# 6502.net
KiCad netlist of a schematic drawn in EasyEDA
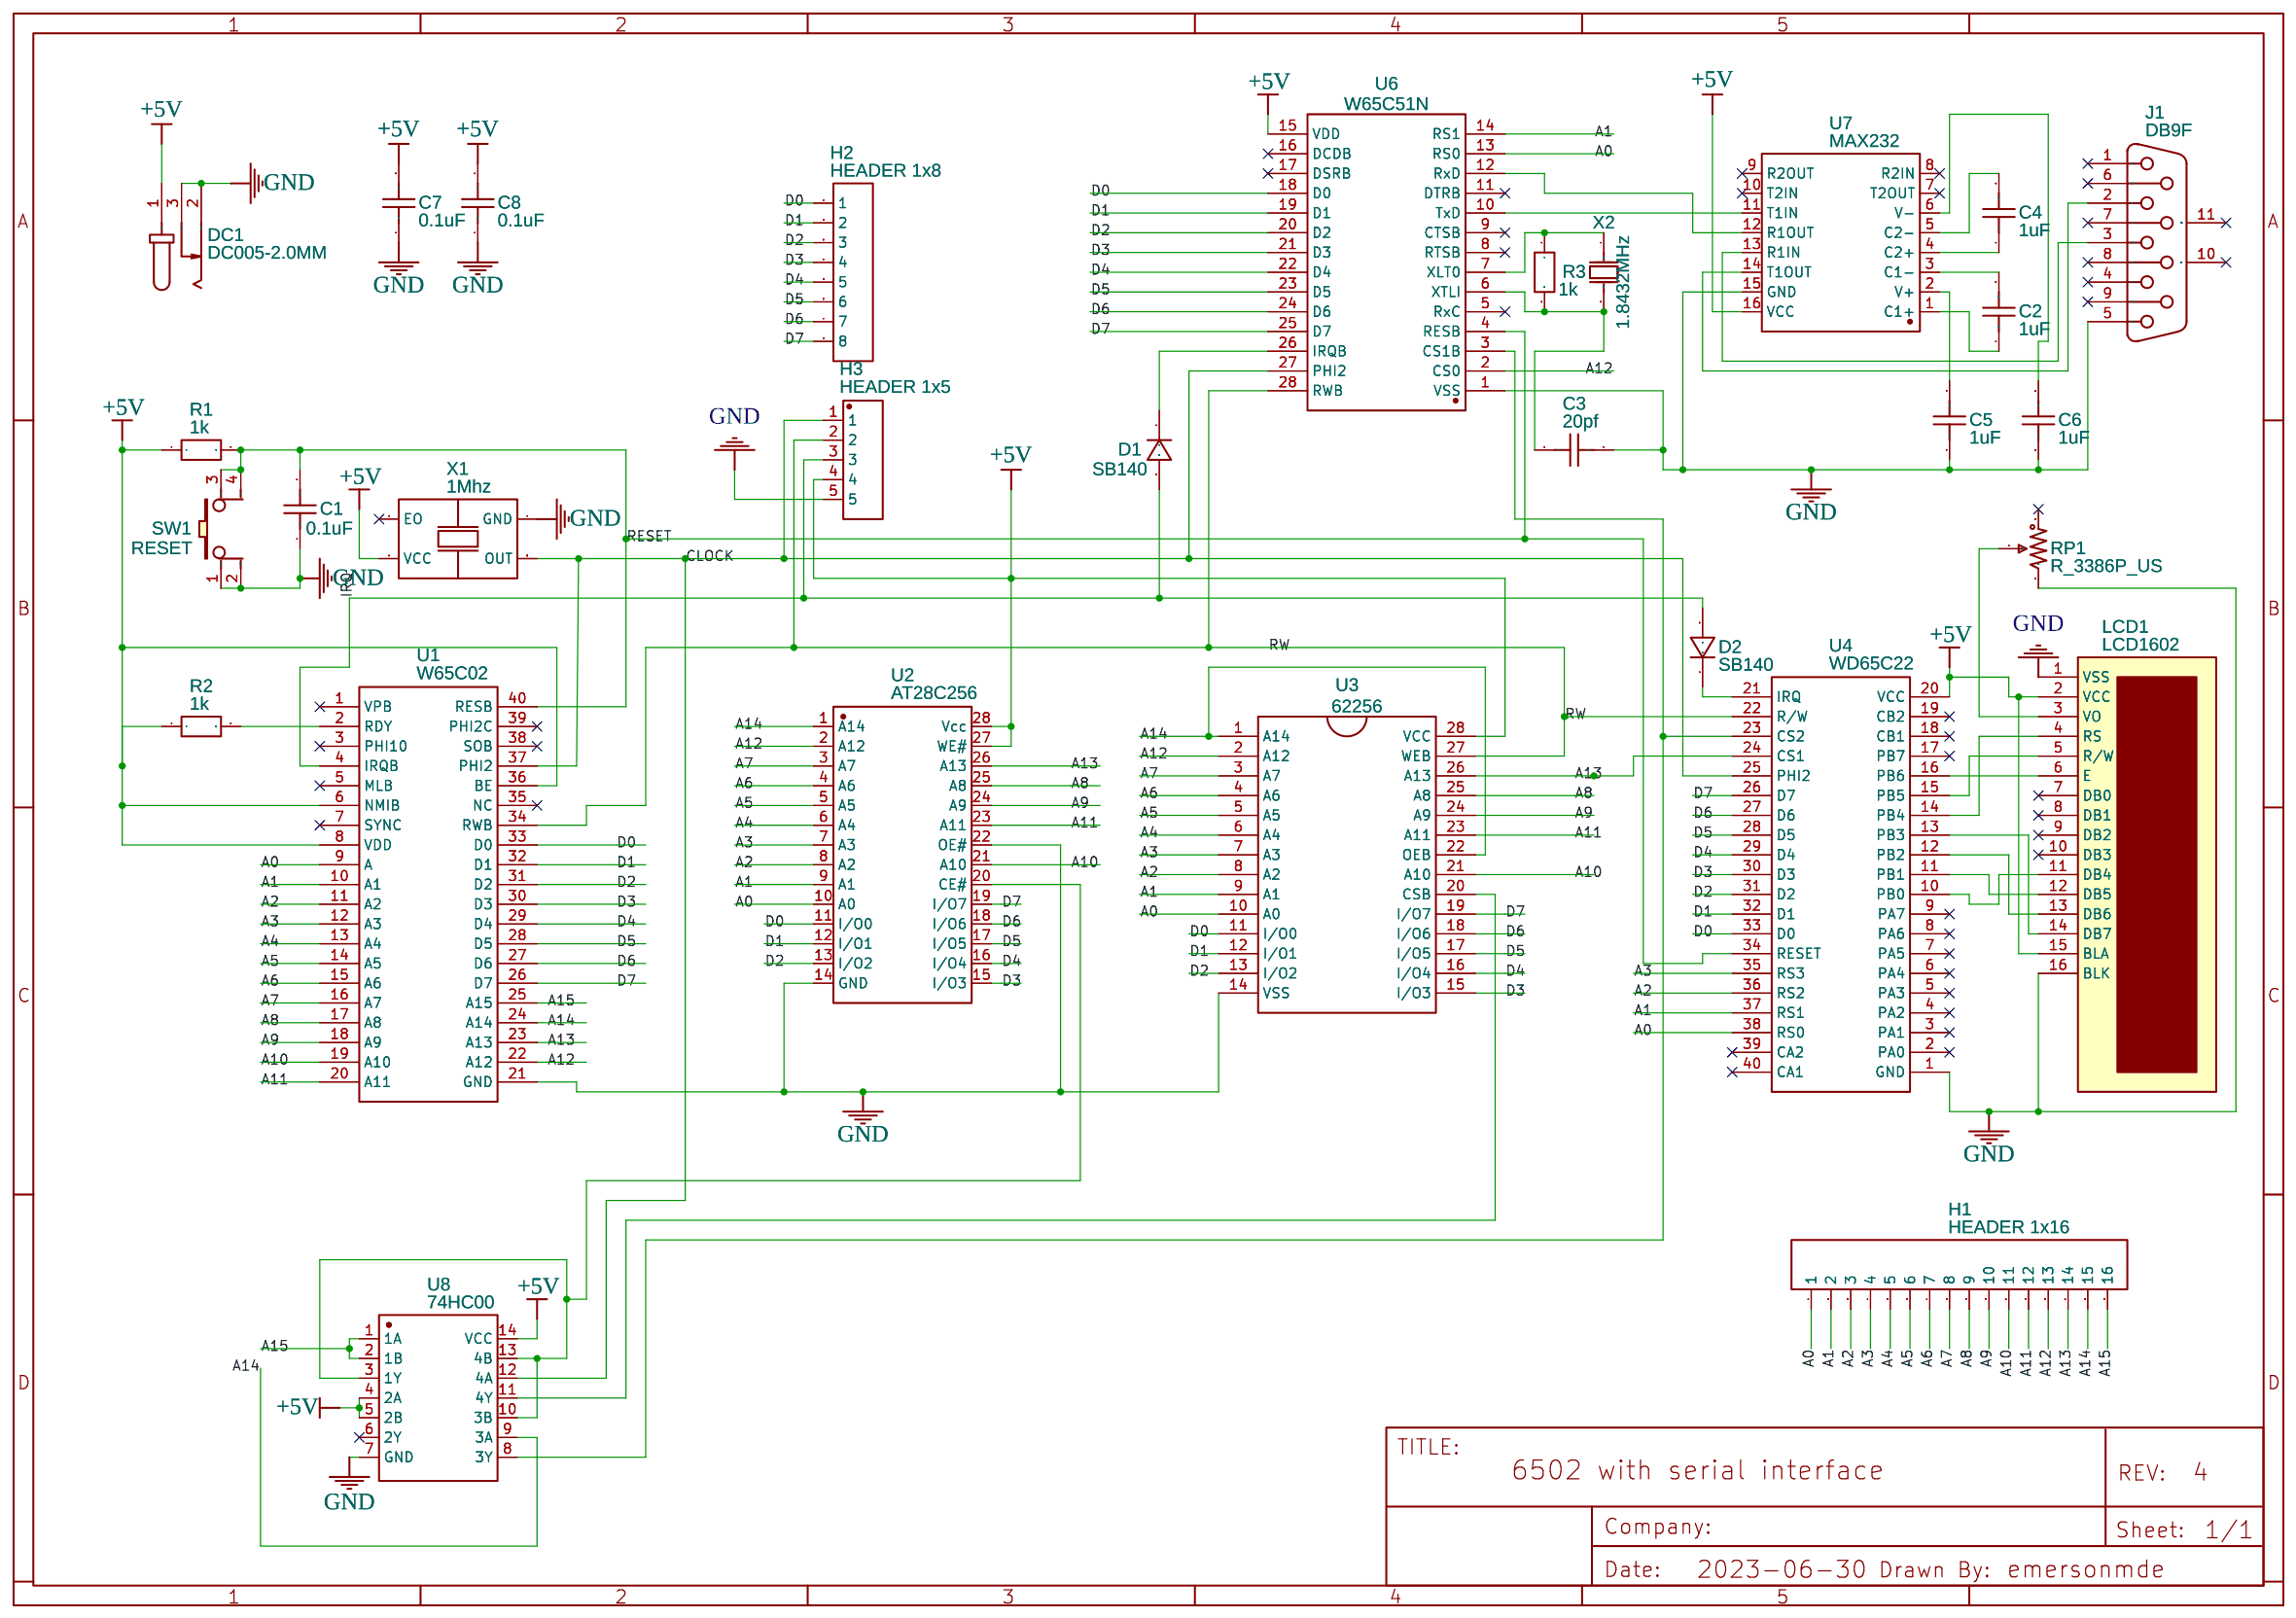
[diagram p0: schematic sheet]

(export (version "E")
  (design (tool "Eeschema 10.0.6"))
  (components
    (comp (ref "C1") (value "0.1uF") (libsource (lib "") (part "C_0603_US")))
    (comp (ref "C2") (value "1uF") (libsource (lib "") (part "C_0603_US")))
    (comp (ref "C3") (value "20pf") (libsource (lib "") (part "C_0603_US_1")))
    (comp (ref "C4") (value "1uF") (libsource (lib "") (part "C_0603_US")))
    (comp (ref "C5") (value "1uF") (libsource (lib "") (part "C_0603_US")))
    (comp (ref "C6") (value "1uF") (libsource (lib "") (part "C_0603_US")))
    (comp (ref "C7") (value "0.1uF") (libsource (lib "") (part "C_0603_US")))
    (comp (ref "C8") (value "0.1uF") (libsource (lib "") (part "C_0603_US")))
    (comp (ref "D1")
      (value "SB140")
      (fields (field (name "BOM_Manufacturer Part") "1N4007W") (field (name "BOM_Supplier Part") "C328592"))
      (libsource (lib "") (part "1N4007W"))
    )
    (comp (ref "D2")
      (value "SB140")
      (fields (field (name "BOM_Manufacturer Part") "1N4007W") (field (name "BOM_Supplier Part") "C328592"))
      (libsource (lib "") (part "1N4007W_1"))
    )
    (comp (ref "DC1")
      (value "DC005-2.0MM")
      (fields (field (name "BOM_Supplier Part") "C111567"))
      (libsource (lib "") (part "DC005-2.0MM"))
    )
    (comp (ref "H1")
      (value "HEADER 1x16")
      (fields
        (field (name "BOM_Manufacturer Part") "2.54-1*16P母")
        (field (name "BOM_Supplier Part") "C66987")
      )
      (libsource (lib "") (part "Header-Female-2.54_1x16"))
    )
    (comp (ref "H2")
      (value "HEADER 1x8")
      (fields
        (field (name "BOM_Manufacturer Part") "2.54-1*8P母环保")
        (field (name "BOM_Supplier Part") "C27438")
      )
      (libsource (lib "") (part "Header-Female-2.54_1x8"))
    )
    (comp (ref "H3") (value "HEADER 1x5") (libsource (lib "") (part "HEADER - 2.54_1X5")))
    (comp (ref "J1")
      (value "DB9F")
      (fields (field (name "BOM_Supplier Part") "C9900018961"))
      (libsource (lib "") (part "DB9F"))
    )
    (comp (ref "LCD1")
      (value "LCD1602")
      (fields
        (field (name "BOM_Manufacturer Part") "LCM1602K-NSW-BBW")
        (field (name "BOM_Supplier Part") "C83275")
      )
      (libsource (lib "") (part "LCD1602"))
    )
    (comp (ref "R1") (value "1k") (libsource (lib "") (part "R_0603_EU")))
    (comp (ref "R2") (value "1k") (libsource (lib "") (part "R_0603_EU")))
    (comp (ref "R3") (value "1k") (libsource (lib "") (part "R_0603_EU_1")))
    (comp (ref "RP1") (value "R_3386P_US") (libsource (lib "") (part "R_3386P_US")))
    (comp (ref "SW1")
      (value "RESET")
      (fields
        (field (name "BOM_Manufacturer Part") "button6*6*8.5")
        (field (name "BOM_Supplier Part") "C59980")
      )
      (libsource (lib "") (part "button6*6*8.5"))
    )
    (comp (ref "U1") (value "W65C02") (libsource (lib "") (part "W65C02")))
    (comp (ref "U2")
      (value "AT28C256")
      (fields
        (field (name "BOM_Manufacturer Part") "AT28C256-15DM/883-815")
        (field (name "BOM_Supplier Part") "C612358")
      )
      (libsource (lib "") (part "AT28C256-15DM/883-815"))
    )
    (comp (ref "U3") (value "62256") (libsource (lib "") (part "HM62256B")))
    (comp (ref "U4") (value "WD65C22") (libsource (lib "") (part "WD65C22")))
    (comp (ref "U6")
      (value "W65C51N")
      (fields
        (field (name "BOM_Manufacturer Part") "W65C51N6TPG-14")
        (field (name "BOM_Supplier Part") "955-W65C51N6TPG-14")
      )
      (libsource (lib "") (part "W65C51N6TPG-14"))
    )
    (comp (ref "U7")
      (value "MAX232")
      (fields
        (field (name "BOM_Manufacturer Part") "MAX232AEPE+")
        (field (name "BOM_Supplier Part") "C242610")
      )
      (libsource (lib "") (part "MAX232AEPE+"))
    )
    (comp (ref "U8")
      (value "74HC00")
      (fields (field (name "BOM_Manufacturer Part") "SN74HC00N") (field (name "BOM_Supplier Part") "C2902"))
      (libsource (lib "") (part "SN74HC00N"))
    )
    (comp (ref "X1")
      (value "1Mhz")
      (fields
        (field (name "BOM_Manufacturer Part") "MXO45-3C-7M372800")
        (field (name "BOM_Supplier Part") "110-MXO45-3C-7M372800-ND")
      )
      (libsource (lib "") (part "Full Can Oscillator Crystal"))
    )
    (comp (ref "X2")
      (value "1.8432MHz")
      (fields
        (field (name "BOM_Manufacturer Part") "X49UD18432MSD2SC-1")
        (field (name "BOM_Supplier Part") "C2179")
      )
      (libsource (lib "") (part "X49UD18432MSD2SC-1 COPY"))
    )
  )
  (nets
    (net (code "1") (name "+5V") (class "Default")
      (node (ref "C7") (pin "2") (pinfunction "2_2") (pintype "unspecified"))
      (node (ref "C8") (pin "2") (pinfunction "2_2") (pintype "unspecified"))
      (node (ref "DC1") (pin "1") (pinfunction "1_1") (pintype "unspecified"))
      (node (ref "H3") (pin "4") (pinfunction "4_4") (pintype "unspecified"))
      (node (ref "LCD1") (pin "15") (pinfunction "BLA_15") (pintype "unspecified"))
      (node (ref "LCD1") (pin "2") (pinfunction "VCC_2") (pintype "unspecified"))
      (node (ref "R1") (pin "1") (pinfunction "1_1") (pintype "unspecified"))
      (node (ref "R2") (pin "1") (pinfunction "1_1") (pintype "unspecified"))
      (node (ref "U1") (pin "36") (pinfunction "BE_36") (pintype "unspecified"))
      (node (ref "U1") (pin "6") (pinfunction "NMIB_6") (pintype "unspecified"))
      (node (ref "U1") (pin "8") (pinfunction "VDD_8") (pintype "unspecified"))
      (node (ref "U2") (pin "27") (pinfunction "WE#_27") (pintype "unspecified"))
      (node (ref "U2") (pin "28") (pinfunction "Vcc_28") (pintype "unspecified"))
      (node (ref "U3") (pin "28") (pinfunction "VCC_28") (pintype "unspecified"))
      (node (ref "U4") (pin "20") (pinfunction "VCC_20") (pintype "unspecified"))
      (node (ref "U6") (pin "15") (pinfunction "VDD_15") (pintype "passive"))
      (node (ref "U7") (pin "16") (pinfunction "VCC_16") (pintype "unspecified"))
      (node (ref "U8") (pin "14") (pinfunction "VCC_14") (pintype "unspecified"))
      (node (ref "U8") (pin "4") (pinfunction "2A_4") (pintype "unspecified"))
      (node (ref "U8") (pin "5") (pinfunction "2B_5") (pintype "unspecified"))
      (node (ref "X1") (pin "14") (pinfunction "VCC_14") (pintype "unspecified"))
    )
    (net (code "2") (name "/A0") (class "Default")
      (node (ref "H1") (pin "1") (pinfunction "1_1") (pintype "input"))
      (node (ref "U1") (pin "9") (pinfunction "A_9") (pintype "unspecified"))
      (node (ref "U2") (pin "10") (pinfunction "A0_10") (pintype "unspecified"))
      (node (ref "U3") (pin "10") (pinfunction "A0_10") (pintype "unspecified"))
      (node (ref "U4") (pin "38") (pinfunction "RS0_38") (pintype "unspecified"))
      (node (ref "U6") (pin "13") (pinfunction "RS0_13") (pintype "unspecified"))
    )
    (net (code "3") (name "/A1") (class "Default")
      (node (ref "H1") (pin "2") (pinfunction "2_2") (pintype "input"))
      (node (ref "U1") (pin "10") (pinfunction "A1_10") (pintype "unspecified"))
      (node (ref "U2") (pin "9") (pinfunction "A1_9") (pintype "unspecified"))
      (node (ref "U3") (pin "9") (pinfunction "A1_9") (pintype "unspecified"))
      (node (ref "U4") (pin "37") (pinfunction "RS1_37") (pintype "unspecified"))
      (node (ref "U6") (pin "14") (pinfunction "RS1_14") (pintype "unspecified"))
    )
    (net (code "4") (name "/A2") (class "Default")
      (node (ref "H1") (pin "3") (pinfunction "3_3") (pintype "input"))
      (node (ref "U1") (pin "11") (pinfunction "A2_11") (pintype "unspecified"))
      (node (ref "U2") (pin "8") (pinfunction "A2_8") (pintype "unspecified"))
      (node (ref "U3") (pin "8") (pinfunction "A2_8") (pintype "unspecified"))
      (node (ref "U4") (pin "36") (pinfunction "RS2_36") (pintype "unspecified"))
    )
    (net (code "5") (name "/A3") (class "Default")
      (node (ref "H1") (pin "4") (pinfunction "4_4") (pintype "input"))
      (node (ref "U1") (pin "12") (pinfunction "A3_12") (pintype "unspecified"))
      (node (ref "U2") (pin "7") (pinfunction "A3_7") (pintype "unspecified"))
      (node (ref "U3") (pin "7") (pinfunction "A3_7") (pintype "unspecified"))
      (node (ref "U4") (pin "35") (pinfunction "RS3_35") (pintype "unspecified"))
    )
    (net (code "6") (name "/A4") (class "Default")
      (node (ref "H1") (pin "5") (pinfunction "5_5") (pintype "input"))
      (node (ref "U1") (pin "13") (pinfunction "A4_13") (pintype "unspecified"))
      (node (ref "U2") (pin "6") (pinfunction "A4_6") (pintype "unspecified"))
      (node (ref "U3") (pin "6") (pinfunction "A4_6") (pintype "unspecified"))
    )
    (net (code "7") (name "/A5") (class "Default")
      (node (ref "H1") (pin "6") (pinfunction "6_6") (pintype "input"))
      (node (ref "U1") (pin "14") (pinfunction "A5_14") (pintype "unspecified"))
      (node (ref "U2") (pin "5") (pinfunction "A5_5") (pintype "unspecified"))
      (node (ref "U3") (pin "5") (pinfunction "A5_5") (pintype "unspecified"))
    )
    (net (code "8") (name "/A6") (class "Default")
      (node (ref "H1") (pin "7") (pinfunction "7_7") (pintype "input"))
      (node (ref "U1") (pin "15") (pinfunction "A6_15") (pintype "unspecified"))
      (node (ref "U2") (pin "4") (pinfunction "A6_4") (pintype "unspecified"))
      (node (ref "U3") (pin "4") (pinfunction "A6_4") (pintype "unspecified"))
    )
    (net (code "9") (name "/A7") (class "Default")
      (node (ref "H1") (pin "8") (pinfunction "8_8") (pintype "input"))
      (node (ref "U1") (pin "16") (pinfunction "A7_16") (pintype "unspecified"))
      (node (ref "U2") (pin "3") (pinfunction "A7_3") (pintype "unspecified"))
      (node (ref "U3") (pin "3") (pinfunction "A7_3") (pintype "unspecified"))
    )
    (net (code "10") (name "/A8") (class "Default")
      (node (ref "H1") (pin "9") (pinfunction "9_9") (pintype "input"))
      (node (ref "U1") (pin "17") (pinfunction "A8_17") (pintype "unspecified"))
      (node (ref "U2") (pin "25") (pinfunction "A8_25") (pintype "unspecified"))
      (node (ref "U3") (pin "25") (pinfunction "A8_25") (pintype "unspecified"))
    )
    (net (code "11") (name "/A9") (class "Default")
      (node (ref "H1") (pin "10") (pinfunction "10_10") (pintype "input"))
      (node (ref "U1") (pin "18") (pinfunction "A9_18") (pintype "unspecified"))
      (node (ref "U2") (pin "24") (pinfunction "A9_24") (pintype "unspecified"))
      (node (ref "U3") (pin "24") (pinfunction "A9_24") (pintype "unspecified"))
    )
    (net (code "12") (name "/A10") (class "Default")
      (node (ref "H1") (pin "11") (pinfunction "11_11") (pintype "input"))
      (node (ref "U1") (pin "19") (pinfunction "A10_19") (pintype "unspecified"))
      (node (ref "U2") (pin "21") (pinfunction "A10_21") (pintype "unspecified"))
      (node (ref "U3") (pin "21") (pinfunction "A10_21") (pintype "unspecified"))
    )
    (net (code "13") (name "/A11") (class "Default")
      (node (ref "H1") (pin "12") (pinfunction "12_12") (pintype "input"))
      (node (ref "U1") (pin "20") (pinfunction "A11_20") (pintype "unspecified"))
      (node (ref "U2") (pin "23") (pinfunction "A11_23") (pintype "unspecified"))
      (node (ref "U3") (pin "23") (pinfunction "A11_23") (pintype "unspecified"))
    )
    (net (code "14") (name "/A12") (class "Default")
      (node (ref "H1") (pin "13") (pinfunction "13_13") (pintype "input"))
      (node (ref "U1") (pin "22") (pinfunction "A12_22") (pintype "unspecified"))
      (node (ref "U2") (pin "2") (pinfunction "A12_2") (pintype "unspecified"))
      (node (ref "U3") (pin "2") (pinfunction "A12_2") (pintype "unspecified"))
      (node (ref "U6") (pin "2") (pinfunction "CS0_2") (pintype "unspecified"))
    )
    (net (code "15") (name "/A13") (class "Default")
      (node (ref "H1") (pin "14") (pinfunction "14_14") (pintype "input"))
      (node (ref "U1") (pin "23") (pinfunction "A13_23") (pintype "unspecified"))
      (node (ref "U2") (pin "26") (pinfunction "A13_26") (pintype "unspecified"))
      (node (ref "U3") (pin "26") (pinfunction "A13_26") (pintype "unspecified"))
      (node (ref "U4") (pin "24") (pinfunction "CS1_24") (pintype "unspecified"))
    )
    (net (code "16") (name "/A14") (class "Default")
      (node (ref "H1") (pin "15") (pinfunction "15_15") (pintype "input"))
      (node (ref "U1") (pin "24") (pinfunction "A14_24") (pintype "unspecified"))
      (node (ref "U2") (pin "1") (pinfunction "A14_1") (pintype "unspecified"))
      (node (ref "U3") (pin "1") (pinfunction "A14_1") (pintype "unspecified"))
      (node (ref "U3") (pin "22") (pinfunction "OEB_22") (pintype "unspecified"))
      (node (ref "U8") (pin "9") (pinfunction "3A_9") (pintype "unspecified"))
    )
    (net (code "17") (name "/A15") (class "Default")
      (node (ref "H1") (pin "16") (pinfunction "16_16") (pintype "input"))
      (node (ref "U1") (pin "25") (pinfunction "A15_25") (pintype "unspecified"))
      (node (ref "U8") (pin "1") (pinfunction "1A_1") (pintype "unspecified"))
      (node (ref "U8") (pin "2") (pinfunction "1B_2") (pintype "unspecified"))
    )
    (net (code "18") (name "/CLOCK") (class "Default")
      (node (ref "H3") (pin "1") (pinfunction "1_1") (pintype "unspecified"))
      (node (ref "U1") (pin "37") (pinfunction "PHI2_37") (pintype "unspecified"))
      (node (ref "U4") (pin "25") (pinfunction "PHI2_25") (pintype "unspecified"))
      (node (ref "U6") (pin "27") (pinfunction "PHI2_27") (pintype "input"))
      (node (ref "U8") (pin "12") (pinfunction "4A_12") (pintype "unspecified"))
      (node (ref "X1") (pin "8") (pinfunction "OUT_8") (pintype "unspecified"))
    )
    (net (code "19") (name "/D0") (class "Default")
      (node (ref "H2") (pin "1") (pinfunction "1_1") (pintype "input"))
      (node (ref "U1") (pin "33") (pinfunction "D0_33") (pintype "unspecified"))
      (node (ref "U2") (pin "11") (pinfunction "I/O0_11") (pintype "unspecified"))
      (node (ref "U3") (pin "11") (pinfunction "I/O0_11") (pintype "unspecified"))
      (node (ref "U4") (pin "33") (pinfunction "D0_33") (pintype "unspecified"))
      (node (ref "U6") (pin "18") (pinfunction "D0_18") (pintype "bidirectional"))
    )
    (net (code "20") (name "/D1") (class "Default")
      (node (ref "H2") (pin "2") (pinfunction "2_2") (pintype "input"))
      (node (ref "U1") (pin "32") (pinfunction "D1_32") (pintype "unspecified"))
      (node (ref "U2") (pin "12") (pinfunction "I/O1_12") (pintype "unspecified"))
      (node (ref "U3") (pin "12") (pinfunction "I/O1_12") (pintype "unspecified"))
      (node (ref "U4") (pin "32") (pinfunction "D1_32") (pintype "unspecified"))
      (node (ref "U6") (pin "19") (pinfunction "D1_19") (pintype "bidirectional"))
    )
    (net (code "21") (name "/D2") (class "Default")
      (node (ref "H2") (pin "3") (pinfunction "3_3") (pintype "input"))
      (node (ref "U1") (pin "31") (pinfunction "D2_31") (pintype "unspecified"))
      (node (ref "U2") (pin "13") (pinfunction "I/O2_13") (pintype "unspecified"))
      (node (ref "U3") (pin "13") (pinfunction "I/O2_13") (pintype "unspecified"))
      (node (ref "U4") (pin "31") (pinfunction "D2_31") (pintype "unspecified"))
      (node (ref "U6") (pin "20") (pinfunction "D2_20") (pintype "bidirectional"))
    )
    (net (code "22") (name "/D3") (class "Default")
      (node (ref "H2") (pin "4") (pinfunction "4_4") (pintype "input"))
      (node (ref "U1") (pin "30") (pinfunction "D3_30") (pintype "unspecified"))
      (node (ref "U2") (pin "15") (pinfunction "I/O3_15") (pintype "unspecified"))
      (node (ref "U3") (pin "15") (pinfunction "I/O3_15") (pintype "unspecified"))
      (node (ref "U4") (pin "30") (pinfunction "D3_30") (pintype "unspecified"))
      (node (ref "U6") (pin "21") (pinfunction "D3_21") (pintype "bidirectional"))
    )
    (net (code "23") (name "/D4") (class "Default")
      (node (ref "H2") (pin "5") (pinfunction "5_5") (pintype "input"))
      (node (ref "U1") (pin "29") (pinfunction "D4_29") (pintype "unspecified"))
      (node (ref "U2") (pin "16") (pinfunction "I/O4_16") (pintype "unspecified"))
      (node (ref "U3") (pin "16") (pinfunction "I/O4_16") (pintype "unspecified"))
      (node (ref "U4") (pin "29") (pinfunction "D4_29") (pintype "unspecified"))
      (node (ref "U6") (pin "22") (pinfunction "D4_22") (pintype "bidirectional"))
    )
    (net (code "24") (name "/D5") (class "Default")
      (node (ref "H2") (pin "6") (pinfunction "6_6") (pintype "input"))
      (node (ref "U1") (pin "28") (pinfunction "D5_28") (pintype "unspecified"))
      (node (ref "U2") (pin "17") (pinfunction "I/O5_17") (pintype "unspecified"))
      (node (ref "U3") (pin "17") (pinfunction "I/O5_17") (pintype "unspecified"))
      (node (ref "U4") (pin "28") (pinfunction "D5_28") (pintype "unspecified"))
      (node (ref "U6") (pin "23") (pinfunction "D5_23") (pintype "bidirectional"))
    )
    (net (code "25") (name "/D6") (class "Default")
      (node (ref "H2") (pin "7") (pinfunction "7_7") (pintype "input"))
      (node (ref "U1") (pin "27") (pinfunction "D6_27") (pintype "unspecified"))
      (node (ref "U2") (pin "18") (pinfunction "I/O6_18") (pintype "unspecified"))
      (node (ref "U3") (pin "18") (pinfunction "I/O6_18") (pintype "unspecified"))
      (node (ref "U4") (pin "27") (pinfunction "D6_27") (pintype "unspecified"))
      (node (ref "U6") (pin "24") (pinfunction "D6_24") (pintype "bidirectional"))
    )
    (net (code "26") (name "/D7") (class "Default")
      (node (ref "H2") (pin "8") (pinfunction "8_8") (pintype "input"))
      (node (ref "U1") (pin "26") (pinfunction "D7_26") (pintype "unspecified"))
      (node (ref "U2") (pin "19") (pinfunction "I/O7_19") (pintype "unspecified"))
      (node (ref "U3") (pin "19") (pinfunction "I/O7_19") (pintype "unspecified"))
      (node (ref "U4") (pin "26") (pinfunction "D7_26") (pintype "unspecified"))
      (node (ref "U6") (pin "25") (pinfunction "D7_25") (pintype "bidirectional"))
    )
    (net (code "27") (name "/IRQ") (class "Default")
      (node (ref "D1") (pin "2") (pinfunction "2_2") (pintype "unspecified"))
      (node (ref "D2") (pin "2") (pinfunction "2_2") (pintype "unspecified"))
      (node (ref "H3") (pin "3") (pinfunction "3_3") (pintype "unspecified"))
      (node (ref "U1") (pin "4") (pinfunction "IRQB_4") (pintype "unspecified"))
    )
    (net (code "28") (name "/RESET") (class "Default")
      (node (ref "C1") (pin "2") (pinfunction "2_2") (pintype "unspecified"))
      (node (ref "R1") (pin "2") (pinfunction "2_2") (pintype "unspecified"))
      (node (ref "SW1") (pin "3") (pinfunction "3_3") (pintype "input"))
      (node (ref "SW1") (pin "4") (pinfunction "4_4") (pintype "input"))
      (node (ref "U1") (pin "40") (pinfunction "RESB_40") (pintype "unspecified"))
      (node (ref "U4") (pin "34") (pinfunction "RESET_34") (pintype "unspecified"))
      (node (ref "U6") (pin "4") (pinfunction "RESB_4") (pintype "unspecified"))
    )
    (net (code "29") (name "/RW") (class "Default")
      (node (ref "H3") (pin "2") (pinfunction "2_2") (pintype "unspecified"))
      (node (ref "U1") (pin "34") (pinfunction "RWB_34") (pintype "unspecified"))
      (node (ref "U3") (pin "27") (pinfunction "WEB_27") (pintype "unspecified"))
      (node (ref "U4") (pin "22") (pinfunction "R/W_22") (pintype "unspecified"))
      (node (ref "U6") (pin "28") (pinfunction "RWB_28") (pintype "input"))
    )
    (net (code "30") (name "GND") (class "Default")
      (node (ref "C1") (pin "1") (pinfunction "1_1") (pintype "unspecified"))
      (node (ref "C3") (pin "1") (pinfunction "1_1") (pintype "unspecified"))
      (node (ref "C5") (pin "1") (pinfunction "1_1") (pintype "unspecified"))
      (node (ref "C6") (pin "1") (pinfunction "1_1") (pintype "unspecified"))
      (node (ref "C7") (pin "1") (pinfunction "1_1") (pintype "unspecified"))
      (node (ref "C8") (pin "1") (pinfunction "1_1") (pintype "unspecified"))
      (node (ref "DC1") (pin "2") (pinfunction "2_2") (pintype "unspecified"))
      (node (ref "DC1") (pin "3") (pinfunction "3_3") (pintype "unspecified"))
      (node (ref "H3") (pin "5") (pinfunction "5_5") (pintype "unspecified"))
      (node (ref "J1") (pin "5") (pinfunction "5_5") (pintype "input"))
      (node (ref "LCD1") (pin "1") (pinfunction "VSS_1") (pintype "unspecified"))
      (node (ref "LCD1") (pin "16") (pinfunction "BLK_16") (pintype "unspecified"))
      (node (ref "RP1") (pin "3") (pinfunction "3_3") (pintype "unspecified"))
      (node (ref "SW1") (pin "1") (pinfunction "1_1") (pintype "input"))
      (node (ref "SW1") (pin "2") (pinfunction "2_2") (pintype "input"))
      (node (ref "U1") (pin "21") (pinfunction "GND_21") (pintype "unspecified"))
      (node (ref "U2") (pin "14") (pinfunction "GND_14") (pintype "unspecified"))
      (node (ref "U2") (pin "22") (pinfunction "OE#_22") (pintype "unspecified"))
      (node (ref "U3") (pin "14") (pinfunction "VSS_14") (pintype "unspecified"))
      (node (ref "U4") (pin "1") (pinfunction "GND_1") (pintype "unspecified"))
      (node (ref "U6") (pin "1") (pinfunction "VSS_1") (pintype "passive"))
      (node (ref "U7") (pin "15") (pinfunction "GND_15") (pintype "unspecified"))
      (node (ref "U8") (pin "7") (pinfunction "GND_7") (pintype "unspecified"))
      (node (ref "X1") (pin "7") (pinfunction "GND_7") (pintype "unspecified"))
    )
    (net (code "31") (name "Net-(LCD1-DB4)") (class "Default")
      (node (ref "LCD1") (pin "11") (pinfunction "DB4_11") (pintype "unspecified"))
      (node (ref "U4") (pin "10") (pinfunction "PB0_10") (pintype "unspecified"))
    )
    (net (code "32") (name "Net-(LCD1-DB5)") (class "Default")
      (node (ref "LCD1") (pin "12") (pinfunction "DB5_12") (pintype "unspecified"))
      (node (ref "U4") (pin "11") (pinfunction "PB1_11") (pintype "unspecified"))
    )
    (net (code "33") (name "Net-(LCD1-DB6)") (class "Default")
      (node (ref "LCD1") (pin "13") (pinfunction "DB6_13") (pintype "unspecified"))
      (node (ref "U4") (pin "12") (pinfunction "PB2_12") (pintype "unspecified"))
    )
    (net (code "34") (name "Net-(LCD1-DB7)") (class "Default")
      (node (ref "LCD1") (pin "14") (pinfunction "DB7_14") (pintype "unspecified"))
      (node (ref "U4") (pin "13") (pinfunction "PB3_13") (pintype "unspecified"))
    )
    (net (code "35") (name "Net-(LCD1-E)") (class "Default")
      (node (ref "LCD1") (pin "6") (pinfunction "E_6") (pintype "unspecified"))
      (node (ref "U4") (pin "16") (pinfunction "PB6_16") (pintype "unspecified"))
    )
    (net (code "36") (name "Net-(LCD1-RS)") (class "Default")
      (node (ref "LCD1") (pin "4") (pinfunction "RS_4") (pintype "unspecified"))
      (node (ref "U4") (pin "14") (pinfunction "PB4_14") (pintype "unspecified"))
    )
    (net (code "37") (name "Net-(LCD1-R{slash}W)") (class "Default")
      (node (ref "LCD1") (pin "5") (pinfunction "R/W_5") (pintype "unspecified"))
      (node (ref "U4") (pin "15") (pinfunction "PB5_15") (pintype "unspecified"))
    )
    (net (code "38") (name "Net-(LCD1-VO)") (class "Default")
      (node (ref "LCD1") (pin "3") (pinfunction "VO_3") (pintype "unspecified"))
      (node (ref "RP1") (pin "2") (pinfunction "2_2") (pintype "unspecified"))
    )
    (net (code "39") (name "Net-(U1-RDY)") (class "Default")
      (node (ref "R2") (pin "2") (pinfunction "2_2") (pintype "unspecified"))
      (node (ref "U1") (pin "2") (pinfunction "RDY_2") (pintype "unspecified"))
    )
    (net (code "40") (name "Net-(U2-CE#)") (class "Default")
      (node (ref "U2") (pin "20") (pinfunction "CE#_20") (pintype "unspecified"))
      (node (ref "U8") (pin "10") (pinfunction "3B_10") (pintype "unspecified"))
      (node (ref "U8") (pin "13") (pinfunction "4B_13") (pintype "unspecified"))
      (node (ref "U8") (pin "3") (pinfunction "1Y_3") (pintype "unspecified"))
    )
    (net (code "41") (name "Net-(U3-CSB)") (class "Default")
      (node (ref "U3") (pin "20") (pinfunction "CSB_20") (pintype "unspecified"))
      (node (ref "U8") (pin "11") (pinfunction "4Y_11") (pintype "unspecified"))
    )
    (net (code "42") (name "Net-(U4-CS2)") (class "Default")
      (node (ref "U4") (pin "23") (pinfunction "CS2_23") (pintype "unspecified"))
      (node (ref "U6") (pin "3") (pinfunction "CS1B_3") (pintype "unspecified"))
      (node (ref "U8") (pin "8") (pinfunction "3Y_8") (pintype "unspecified"))
    )
    (net (code "43") (name "Net-(U4-IRQ)") (class "Default")
      (node (ref "D2") (pin "1") (pinfunction "1_1") (pintype "unspecified"))
      (node (ref "U4") (pin "21") (pinfunction "IRQ_21") (pintype "unspecified"))
    )
    (net (code "44") (name "Net-(U6-IRQB)") (class "Default")
      (node (ref "D1") (pin "1") (pinfunction "1_1") (pintype "unspecified"))
      (node (ref "U6") (pin "26") (pinfunction "IRQB_26") (pintype "output"))
    )
    (net (code "45") (name "Net-(U6-RxD)") (class "Default")
      (node (ref "U6") (pin "12") (pinfunction "RxD_12") (pintype "unspecified"))
      (node (ref "U7") (pin "12") (pinfunction "R1OUT_12") (pintype "unspecified"))
    )
    (net (code "46") (name "Net-(U6-TxD)") (class "Default")
      (node (ref "U6") (pin "10") (pinfunction "TxD_10") (pintype "unspecified"))
      (node (ref "U7") (pin "11") (pinfunction "T1IN_11") (pintype "unspecified"))
    )
    (net (code "47") (name "Net-(U6-XLT0)") (class "Default")
      (node (ref "R3") (pin "1") (pinfunction "1_1") (pintype "unspecified"))
      (node (ref "U6") (pin "7") (pinfunction "XLT0_7") (pintype "unspecified"))
      (node (ref "X2") (pin "1") (pinfunction "OSC1_1") (pintype "input"))
    )
    (net (code "48") (name "Net-(U6-XTLI)") (class "Default")
      (node (ref "C3") (pin "2") (pinfunction "2_2") (pintype "unspecified"))
      (node (ref "R3") (pin "2") (pinfunction "2_2") (pintype "unspecified"))
      (node (ref "U6") (pin "6") (pinfunction "XTLI_6") (pintype "unspecified"))
      (node (ref "X2") (pin "2") (pinfunction "OSC2_2") (pintype "input"))
    )
    (net (code "49") (name "Net-(U7-C1+)") (class "Default")
      (node (ref "C2") (pin "1") (pinfunction "1_1") (pintype "unspecified"))
      (node (ref "U7") (pin "1") (pinfunction "C1+_1") (pintype "unspecified"))
    )
    (net (code "50") (name "Net-(U7-C1-)") (class "Default")
      (node (ref "C2") (pin "2") (pinfunction "2_2") (pintype "unspecified"))
      (node (ref "U7") (pin "3") (pinfunction "C1-_3") (pintype "unspecified"))
    )
    (net (code "51") (name "Net-(U7-C2+)") (class "Default")
      (node (ref "C4") (pin "1") (pinfunction "1_1") (pintype "unspecified"))
      (node (ref "U7") (pin "4") (pinfunction "C2+_4") (pintype "unspecified"))
    )
    (net (code "52") (name "Net-(U7-C2-)") (class "Default")
      (node (ref "C4") (pin "2") (pinfunction "2_2") (pintype "unspecified"))
      (node (ref "U7") (pin "5") (pinfunction "C2-_5") (pintype "unspecified"))
    )
    (net (code "53") (name "Net-(U7-R1IN)") (class "Default")
      (node (ref "J1") (pin "3") (pinfunction "3_3") (pintype "input"))
      (node (ref "U7") (pin "13") (pinfunction "R1IN_13") (pintype "unspecified"))
    )
    (net (code "54") (name "Net-(U7-T1OUT)") (class "Default")
      (node (ref "J1") (pin "2") (pinfunction "2_2") (pintype "input"))
      (node (ref "U7") (pin "14") (pinfunction "T1OUT_14") (pintype "unspecified"))
    )
    (net (code "55") (name "Net-(U7-V+)") (class "Default")
      (node (ref "C5") (pin "2") (pinfunction "2_2") (pintype "unspecified"))
      (node (ref "U7") (pin "2") (pinfunction "V+_2") (pintype "unspecified"))
    )
    (net (code "56") (name "Net-(U7-V-)") (class "Default")
      (node (ref "C6") (pin "2") (pinfunction "2_2") (pintype "unspecified"))
      (node (ref "U7") (pin "6") (pinfunction "V-_6") (pintype "unspecified"))
    )
    (net (code "57") (name "unconnected-(J1-MH1-Pad10)") (class "Default")
      (node (ref "J1") (pin "10") (pinfunction "MH1_10") (pintype "input+no_connect"))
    )
    (net (code "58") (name "unconnected-(J1-MH2-Pad11)") (class "Default")
      (node (ref "J1") (pin "11") (pinfunction "MH2_11") (pintype "input+no_connect"))
    )
    (net (code "59") (name "unconnected-(J1-Pad1)") (class "Default")
      (node (ref "J1") (pin "1") (pinfunction "1_1") (pintype "input+no_connect"))
    )
    (net (code "60") (name "unconnected-(J1-Pad4)") (class "Default")
      (node (ref "J1") (pin "4") (pinfunction "4_4") (pintype "input+no_connect"))
    )
    (net (code "61") (name "unconnected-(J1-Pad6)") (class "Default")
      (node (ref "J1") (pin "6") (pinfunction "6_6") (pintype "input+no_connect"))
    )
    (net (code "62") (name "unconnected-(J1-Pad7)") (class "Default")
      (node (ref "J1") (pin "7") (pinfunction "7_7") (pintype "input+no_connect"))
    )
    (net (code "63") (name "unconnected-(J1-Pad8)") (class "Default")
      (node (ref "J1") (pin "8") (pinfunction "8_8") (pintype "input+no_connect"))
    )
    (net (code "64") (name "unconnected-(J1-Pad9)") (class "Default")
      (node (ref "J1") (pin "9") (pinfunction "9_9") (pintype "input+no_connect"))
    )
    (net (code "65") (name "unconnected-(LCD1-DB0-Pad7)") (class "Default")
      (node (ref "LCD1") (pin "7") (pinfunction "DB0_7") (pintype "unspecified+no_connect"))
    )
    (net (code "66") (name "unconnected-(LCD1-DB1-Pad8)") (class "Default")
      (node (ref "LCD1") (pin "8") (pinfunction "DB1_8") (pintype "unspecified+no_connect"))
    )
    (net (code "67") (name "unconnected-(LCD1-DB2-Pad9)") (class "Default")
      (node (ref "LCD1") (pin "9") (pinfunction "DB2_9") (pintype "unspecified+no_connect"))
    )
    (net (code "68") (name "unconnected-(LCD1-DB3-Pad10)") (class "Default")
      (node (ref "LCD1") (pin "10") (pinfunction "DB3_10") (pintype "unspecified+no_connect"))
    )
    (net (code "69") (name "unconnected-(RP1-Pad1)") (class "Default")
      (node (ref "RP1") (pin "1") (pinfunction "1_1") (pintype "unspecified+no_connect"))
    )
    (net (code "70") (name "unconnected-(U1-MLB-Pad5)") (class "Default")
      (node (ref "U1") (pin "5") (pinfunction "MLB_5") (pintype "unspecified+no_connect"))
    )
    (net (code "71") (name "unconnected-(U1-NC-Pad35)") (class "Default")
      (node (ref "U1") (pin "35") (pinfunction "NC_35") (pintype "unspecified+no_connect"))
    )
    (net (code "72") (name "unconnected-(U1-PHI2C-Pad39)") (class "Default")
      (node (ref "U1") (pin "39") (pinfunction "PHI2C_39") (pintype "unspecified+no_connect"))
    )
    (net (code "73") (name "unconnected-(U1-PHI10-Pad3)") (class "Default")
      (node (ref "U1") (pin "3") (pinfunction "PHI10_3") (pintype "unspecified+no_connect"))
    )
    (net (code "74") (name "unconnected-(U1-SOB-Pad38)") (class "Default")
      (node (ref "U1") (pin "38") (pinfunction "SOB_38") (pintype "unspecified+no_connect"))
    )
    (net (code "75") (name "unconnected-(U1-SYNC-Pad7)") (class "Default")
      (node (ref "U1") (pin "7") (pinfunction "SYNC_7") (pintype "unspecified+no_connect"))
    )
    (net (code "76") (name "unconnected-(U1-VPB-Pad1)") (class "Default")
      (node (ref "U1") (pin "1") (pinfunction "VPB_1") (pintype "unspecified+no_connect"))
    )
    (net (code "77") (name "unconnected-(U4-CA1-Pad40)") (class "Default")
      (node (ref "U4") (pin "40") (pinfunction "CA1_40") (pintype "unspecified+no_connect"))
    )
    (net (code "78") (name "unconnected-(U4-CA2-Pad39)") (class "Default")
      (node (ref "U4") (pin "39") (pinfunction "CA2_39") (pintype "unspecified+no_connect"))
    )
    (net (code "79") (name "unconnected-(U4-CB1-Pad18)") (class "Default")
      (node (ref "U4") (pin "18") (pinfunction "CB1_18") (pintype "unspecified+no_connect"))
    )
    (net (code "80") (name "unconnected-(U4-CB2-Pad19)") (class "Default")
      (node (ref "U4") (pin "19") (pinfunction "CB2_19") (pintype "unspecified+no_connect"))
    )
    (net (code "81") (name "unconnected-(U4-PA0-Pad2)") (class "Default")
      (node (ref "U4") (pin "2") (pinfunction "PA0_2") (pintype "unspecified+no_connect"))
    )
    (net (code "82") (name "unconnected-(U4-PA1-Pad3)") (class "Default")
      (node (ref "U4") (pin "3") (pinfunction "PA1_3") (pintype "unspecified+no_connect"))
    )
    (net (code "83") (name "unconnected-(U4-PA2-Pad4)") (class "Default")
      (node (ref "U4") (pin "4") (pinfunction "PA2_4") (pintype "unspecified+no_connect"))
    )
    (net (code "84") (name "unconnected-(U4-PA3-Pad5)") (class "Default")
      (node (ref "U4") (pin "5") (pinfunction "PA3_5") (pintype "unspecified+no_connect"))
    )
    (net (code "85") (name "unconnected-(U4-PA4-Pad6)") (class "Default")
      (node (ref "U4") (pin "6") (pinfunction "PA4_6") (pintype "unspecified+no_connect"))
    )
    (net (code "86") (name "unconnected-(U4-PA5-Pad7)") (class "Default")
      (node (ref "U4") (pin "7") (pinfunction "PA5_7") (pintype "unspecified+no_connect"))
    )
    (net (code "87") (name "unconnected-(U4-PA6-Pad8)") (class "Default")
      (node (ref "U4") (pin "8") (pinfunction "PA6_8") (pintype "unspecified+no_connect"))
    )
    (net (code "88") (name "unconnected-(U4-PA7-Pad9)") (class "Default")
      (node (ref "U4") (pin "9") (pinfunction "PA7_9") (pintype "unspecified+no_connect"))
    )
    (net (code "89") (name "unconnected-(U4-PB7-Pad17)") (class "Default")
      (node (ref "U4") (pin "17") (pinfunction "PB7_17") (pintype "unspecified+no_connect"))
    )
    (net (code "90") (name "unconnected-(U6-CTSB-Pad9)") (class "Default")
      (node (ref "U6") (pin "9") (pinfunction "CTSB_9") (pintype "unspecified+no_connect"))
    )
    (net (code "91") (name "unconnected-(U6-DCDB-Pad16)") (class "Default")
      (node (ref "U6") (pin "16") (pinfunction "DCDB_16") (pintype "unspecified+no_connect"))
    )
    (net (code "92") (name "unconnected-(U6-DSRB-Pad17)") (class "Default")
      (node (ref "U6") (pin "17") (pinfunction "DSRB_17") (pintype "unspecified+no_connect"))
    )
    (net (code "93") (name "unconnected-(U6-DTRB-Pad11)") (class "Default")
      (node (ref "U6") (pin "11") (pinfunction "DTRB_11") (pintype "unspecified+no_connect"))
    )
    (net (code "94") (name "unconnected-(U6-RTSB-Pad8)") (class "Default")
      (node (ref "U6") (pin "8") (pinfunction "RTSB_8") (pintype "unspecified+no_connect"))
    )
    (net (code "95") (name "unconnected-(U6-RxC-Pad5)") (class "Default")
      (node (ref "U6") (pin "5") (pinfunction "RxC_5") (pintype "unspecified+no_connect"))
    )
    (net (code "96") (name "unconnected-(U7-R2IN-Pad8)") (class "Default")
      (node (ref "U7") (pin "8") (pinfunction "R2IN_8") (pintype "unspecified+no_connect"))
    )
    (net (code "97") (name "unconnected-(U7-R2OUT-Pad9)") (class "Default")
      (node (ref "U7") (pin "9") (pinfunction "R2OUT_9") (pintype "unspecified+no_connect"))
    )
    (net (code "98") (name "unconnected-(U7-T2IN-Pad10)") (class "Default")
      (node (ref "U7") (pin "10") (pinfunction "T2IN_10") (pintype "unspecified+no_connect"))
    )
    (net (code "99") (name "unconnected-(U7-T2OUT-Pad7)") (class "Default")
      (node (ref "U7") (pin "7") (pinfunction "T2OUT_7") (pintype "unspecified+no_connect"))
    )
    (net (code "100") (name "unconnected-(U8-2Y-Pad6)") (class "Default")
      (node (ref "U8") (pin "6") (pinfunction "2Y_6") (pintype "unspecified+no_connect"))
    )
    (net (code "101") (name "unconnected-(X1-EO-Pad1)") (class "Default")
      (node (ref "X1") (pin "1") (pinfunction "EO_1") (pintype "unspecified+no_connect"))
    )
  )
)
